# CORE.net
KiCad netlist of a schematic drawn in Altium Designer
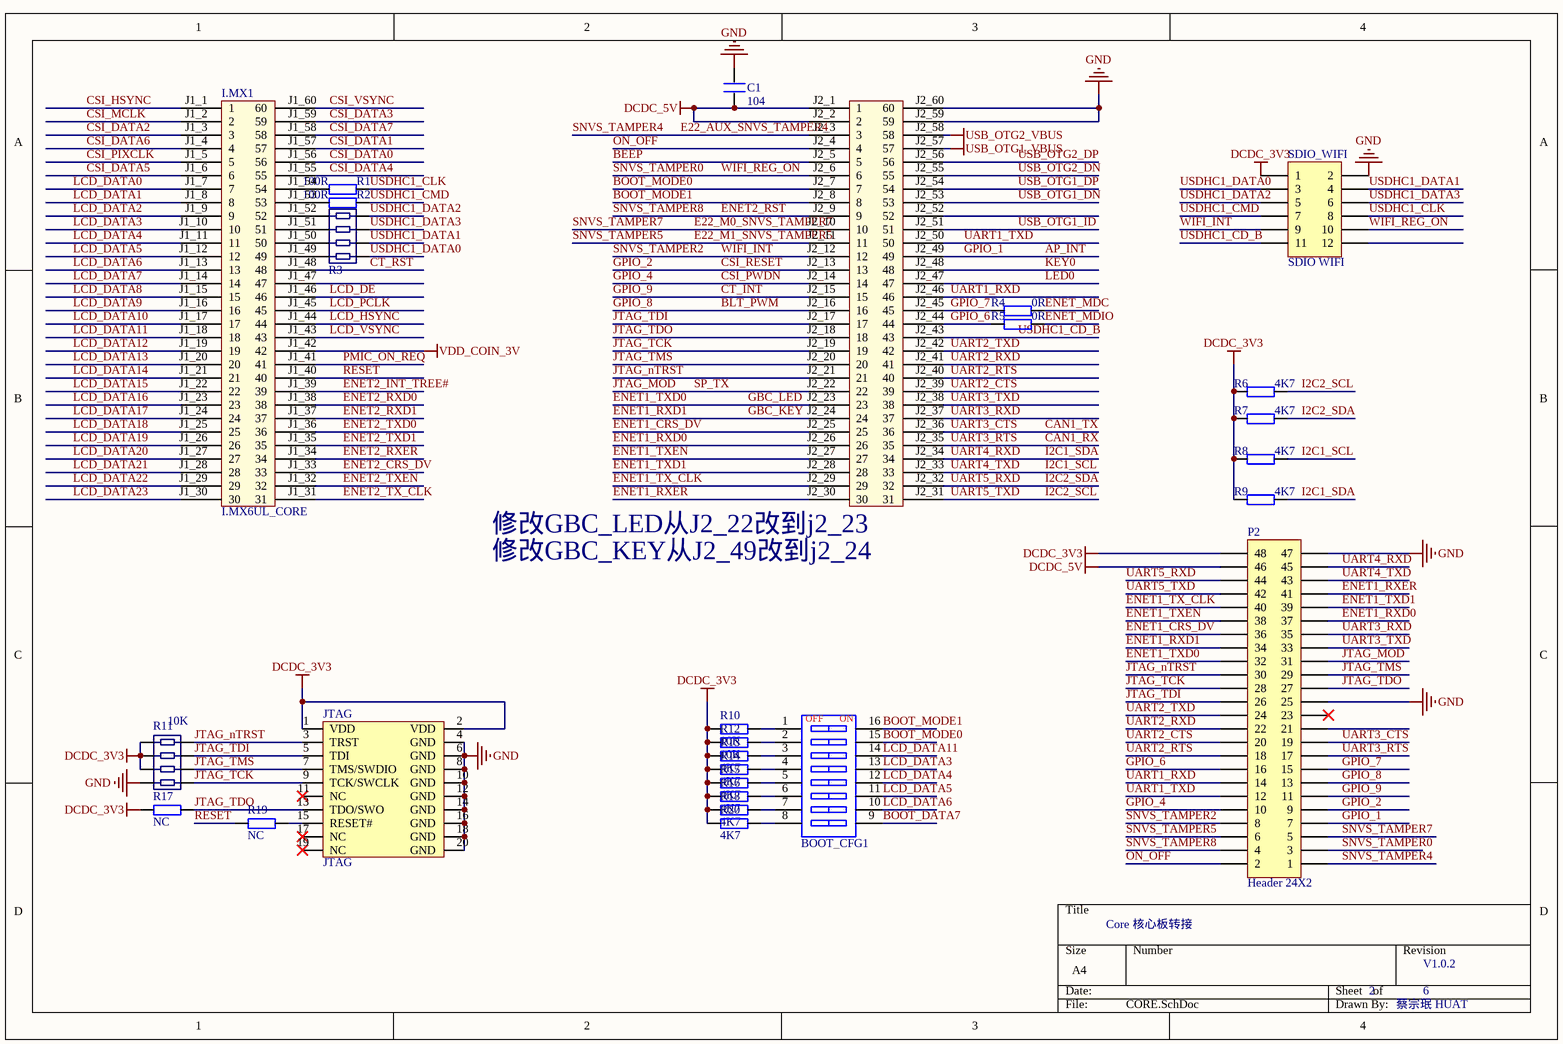
[diagram p0: CORE.SchDoc]

(export (version "E")
  (design (tool "Eeschema 10.0.6"))
  (components
    (comp (ref "BOOT_CFG1")
      (value "CSW-8P")
      (footprint "CSW DIP-8P")
      (description "8路编码开关")
      (fields (field (name "版权归属") "源创客"))
      (libsource (lib "IMX6UL_ALPHA(底板)_V2.0") (part "CSW-8P"))
    )
    (comp (ref "C1") (value "104") (footprint "C_0603P") (libsource (lib "ZZW封装汇总") (part "C")))
    (comp (ref "I.MX1")
      (value "I.MX6UL_CORE")
      (footprint "I.MX6UL_CORE")
      (description "I.MX6UL核心板")
      (libsource (lib "IMX6UL_ALPHA(底板)_V2.0") (part "I.MX6UL核心板"))
    )
    (comp (ref "JTAG") (value "JTAG") (footprint "JTAG_20") (libsource (lib "ZZW封装汇总") (part "JTAG")))
    (comp (ref "P2")
      (value "Header 24X2")
      (footprint "HDR2X24")
      (description "Header, 24-Pin, Dual row")
      (fields (field (name "PUBLISHER") "Altium Limited"))
      (libsource (lib "Miscellaneous Connectors") (part "Header 24X2"))
    )
    (comp (ref "R1") (value "100R") (footprint "R_0603P") (libsource (lib "ZZW封装汇总") (part "R")))
    (comp (ref "R2") (value "100R") (footprint "R_0603P") (libsource (lib "ZZW封装汇总") (part "R")))
    (comp (ref "R3")
      (value "R*4_0603_2")
      (footprint "R*4-0603")
      (libsource (lib "ZZW封装汇总") (part "R*4_0603_2"))
    )
    (comp (ref "R4") (value "0R") (footprint "R_0603P") (libsource (lib "ZZW封装汇总") (part "R")))
    (comp (ref "R5") (value "0R") (footprint "R_0603P") (libsource (lib "ZZW封装汇总") (part "R")))
    (comp (ref "R6") (value "4K7") (footprint "R_0603P") (libsource (lib "ZZW封装汇总") (part "R")))
    (comp (ref "R7") (value "4K7") (footprint "R_0603P") (libsource (lib "ZZW封装汇总") (part "R")))
    (comp (ref "R8") (value "4K7") (footprint "R_0603P") (libsource (lib "ZZW封装汇总") (part "R")))
    (comp (ref "R9") (value "4K7") (footprint "R_0603P") (libsource (lib "ZZW封装汇总") (part "R")))
    (comp (ref "R10") (value "10K") (footprint "R_0603P") (libsource (lib "ZZW封装汇总") (part "R")))
    (comp (ref "R11") (value "10K") (footprint "R*4-0603") (libsource (lib "ZZW封装汇总") (part "R*4_0603_2")))
    (comp (ref "R12") (value "10K") (footprint "R_0603P") (libsource (lib "ZZW封装汇总") (part "R")))
    (comp (ref "R13") (value "4K7") (footprint "R_0603P") (libsource (lib "ZZW封装汇总") (part "R")))
    (comp (ref "R14") (value "4K7") (footprint "R_0603P") (libsource (lib "ZZW封装汇总") (part "R")))
    (comp (ref "R15") (value "4K7") (footprint "R_0603P") (libsource (lib "ZZW封装汇总") (part "R")))
    (comp (ref "R16") (value "4K7") (footprint "R_0603P") (libsource (lib "ZZW封装汇总") (part "R")))
    (comp (ref "R17") (value "NC") (footprint "R_0603P") (libsource (lib "ZZW封装汇总") (part "R")))
    (comp (ref "R18") (value "4K7") (footprint "R_0603P") (libsource (lib "ZZW封装汇总") (part "R")))
    (comp (ref "R19") (value "NC") (footprint "R_0603P") (libsource (lib "ZZW封装汇总") (part "R")))
    (comp (ref "R20") (value "4K7") (footprint "R_0603P") (libsource (lib "ZZW封装汇总") (part "R")))
    (comp (ref "SDIO_WIFI")
      (value "SDIO WIFI")
      (footprint "HDR2X6")
      (description "Header, 6-Pin, Dual row")
      (fields (field (name "PUBLISHER") "Altium Limited"))
      (libsource (lib "IMX6UL_ALPHA(底板)_V2.0") (part "Header 6X2"))
    )
  )
  (nets
    (net (code "1") (name "/AP_INT") (class "Default")
      (node (ref "I.MX1") (pin "J2_49") (pinfunction "49_J2_49") (pintype "passive"))
      (node (ref "P2") (pin "7") (pinfunction "7_7") (pintype "passive"))
    )
    (net (code "2") (name "/BEEP") (class "Default")
      (node (ref "I.MX1") (pin "J2_5") (pinfunction "5_J2_5") (pintype "passive"))
    )
    (net (code "3") (name "/BLT_PWM") (class "Default")
      (node (ref "I.MX1") (pin "J2_16") (pinfunction "16_J2_16") (pintype "passive"))
      (node (ref "P2") (pin "13") (pinfunction "13_13") (pintype "passive"))
    )
    (net (code "4") (name "/BOOT_DATA7") (class "Default")
      (node (ref "BOOT_CFG1") (pin "9") (pinfunction "9_9") (pintype "passive"))
    )
    (net (code "5") (name "/BOOT_MODE0") (class "Default")
      (node (ref "BOOT_CFG1") (pin "15") (pinfunction "15_15") (pintype "passive"))
      (node (ref "I.MX1") (pin "J2_7") (pinfunction "7_J2_7") (pintype "passive"))
    )
    (net (code "6") (name "/BOOT_MODE1") (class "Default")
      (node (ref "BOOT_CFG1") (pin "16") (pinfunction "16_16") (pintype "passive"))
      (node (ref "I.MX1") (pin "J2_8") (pinfunction "8_J2_8") (pintype "passive"))
    )
    (net (code "7") (name "/CAN1_RX") (class "Default")
      (node (ref "I.MX1") (pin "J2_35") (pinfunction "35_J2_35") (pintype "passive"))
      (node (ref "P2") (pin "17") (pinfunction "17_17") (pintype "passive"))
    )
    (net (code "8") (name "/CAN1_TX") (class "Default")
      (node (ref "I.MX1") (pin "J2_36") (pinfunction "36_J2_36") (pintype "passive"))
      (node (ref "P2") (pin "19") (pinfunction "19_19") (pintype "passive"))
    )
    (net (code "9") (name "/CSI_DATA0") (class "Default")
      (node (ref "I.MX1") (pin "J1_56") (pinfunction "56_J1_56") (pintype "passive"))
    )
    (net (code "10") (name "/CSI_DATA1") (class "Default")
      (node (ref "I.MX1") (pin "J1_57") (pinfunction "57_J1_57") (pintype "passive"))
    )
    (net (code "11") (name "/CSI_DATA2") (class "Default")
      (node (ref "I.MX1") (pin "J1_3") (pinfunction "3_J1_3") (pintype "passive"))
    )
    (net (code "12") (name "/CSI_DATA3") (class "Default")
      (node (ref "I.MX1") (pin "J1_59") (pinfunction "59_J1_59") (pintype "passive"))
    )
    (net (code "13") (name "/CSI_DATA4") (class "Default")
      (node (ref "I.MX1") (pin "J1_55") (pinfunction "55_J1_55") (pintype "passive"))
    )
    (net (code "14") (name "/CSI_DATA5") (class "Default")
      (node (ref "I.MX1") (pin "J1_6") (pinfunction "6_J1_6") (pintype "passive"))
    )
    (net (code "15") (name "/CSI_DATA6") (class "Default")
      (node (ref "I.MX1") (pin "J1_4") (pinfunction "4_J1_4") (pintype "passive"))
    )
    (net (code "16") (name "/CSI_DATA7") (class "Default")
      (node (ref "I.MX1") (pin "J1_58") (pinfunction "58_J1_58") (pintype "passive"))
    )
    (net (code "17") (name "/CSI_HSYNC") (class "Default")
      (node (ref "I.MX1") (pin "J1_1") (pinfunction "1_J1_1") (pintype "passive"))
    )
    (net (code "18") (name "/CSI_MCLK") (class "Default")
      (node (ref "I.MX1") (pin "J1_2") (pinfunction "2_J1_2") (pintype "passive"))
    )
    (net (code "19") (name "/CSI_PIXCLK") (class "Default")
      (node (ref "I.MX1") (pin "J1_5") (pinfunction "5_J1_5") (pintype "passive"))
    )
    (net (code "20") (name "/CSI_PWDN") (class "Default")
      (node (ref "I.MX1") (pin "J2_14") (pinfunction "14_J2_14") (pintype "passive"))
      (node (ref "P2") (pin "10") (pinfunction "10_10") (pintype "passive"))
    )
    (net (code "21") (name "/CSI_RESET") (class "Default")
      (node (ref "I.MX1") (pin "J2_13") (pinfunction "13_J2_13") (pintype "passive"))
      (node (ref "P2") (pin "9") (pinfunction "9_9") (pintype "passive"))
    )
    (net (code "22") (name "/CSI_VSYNC") (class "Default")
      (node (ref "I.MX1") (pin "J1_60") (pinfunction "60_J1_60") (pintype "passive"))
    )
    (net (code "23") (name "/CT_INT") (class "Default")
      (node (ref "I.MX1") (pin "J2_15") (pinfunction "15_J2_15") (pintype "passive"))
      (node (ref "P2") (pin "11") (pinfunction "11_11") (pintype "passive"))
    )
    (net (code "24") (name "/CT_RST") (class "Default")
      (node (ref "I.MX1") (pin "J1_48") (pinfunction "48_J1_48") (pintype "passive"))
    )
    (net (code "25") (name "/E22_AUX_SNVS_TAMPER4") (class "Default")
      (node (ref "I.MX1") (pin "J2_3") (pinfunction "3_J2_3") (pintype "passive"))
      (node (ref "P2") (pin "1") (pinfunction "1_1") (pintype "passive"))
    )
    (net (code "26") (name "/E22_M0_SNVS_TAMPER7") (class "Default")
      (node (ref "I.MX1") (pin "J2_10") (pinfunction "10_J2_10") (pintype "passive"))
      (node (ref "P2") (pin "5") (pinfunction "5_5") (pintype "passive"))
    )
    (net (code "27") (name "/E22_M1_SNVS_TAMPER5") (class "Default")
      (node (ref "I.MX1") (pin "J2_11") (pinfunction "11_J2_11") (pintype "passive"))
      (node (ref "P2") (pin "6") (pinfunction "6_6") (pintype "passive"))
    )
    (net (code "28") (name "/ENET1_CRS_DV") (class "Default")
      (node (ref "I.MX1") (pin "J2_25") (pinfunction "25_J2_25") (pintype "passive"))
      (node (ref "P2") (pin "36") (pinfunction "36_36") (pintype "passive"))
    )
    (net (code "29") (name "/ENET1_RXD0") (class "Default")
      (node (ref "I.MX1") (pin "J2_26") (pinfunction "26_J2_26") (pintype "passive"))
      (node (ref "P2") (pin "37") (pinfunction "37_37") (pintype "passive"))
    )
    (net (code "30") (name "/ENET1_RXD1") (class "Default")
      (node (ref "I.MX1") (pin "J2_24") (pinfunction "24_J2_24") (pintype "passive"))
      (node (ref "P2") (pin "34") (pinfunction "34_34") (pintype "passive"))
    )
    (net (code "31") (name "/ENET1_RXER") (class "Default")
      (node (ref "I.MX1") (pin "J2_30") (pinfunction "30_J2_30") (pintype "passive"))
      (node (ref "P2") (pin "41") (pinfunction "41_41") (pintype "passive"))
    )
    (net (code "32") (name "/ENET1_TXD0") (class "Default")
      (node (ref "I.MX1") (pin "J2_23") (pinfunction "23_J2_23") (pintype "passive"))
      (node (ref "P2") (pin "32") (pinfunction "32_32") (pintype "passive"))
    )
    (net (code "33") (name "/ENET1_TXD1") (class "Default")
      (node (ref "I.MX1") (pin "J2_28") (pinfunction "28_J2_28") (pintype "passive"))
      (node (ref "P2") (pin "39") (pinfunction "39_39") (pintype "passive"))
    )
    (net (code "34") (name "/ENET1_TXEN") (class "Default")
      (node (ref "I.MX1") (pin "J2_27") (pinfunction "27_J2_27") (pintype "passive"))
      (node (ref "P2") (pin "38") (pinfunction "38_38") (pintype "passive"))
    )
    (net (code "35") (name "/ENET1_TX_CLK") (class "Default")
      (node (ref "I.MX1") (pin "J2_29") (pinfunction "29_J2_29") (pintype "passive"))
      (node (ref "P2") (pin "40") (pinfunction "40_40") (pintype "passive"))
    )
    (net (code "36") (name "/ENET2_CRS_DV") (class "Default")
      (node (ref "I.MX1") (pin "J1_33") (pinfunction "33_J1_33") (pintype "passive"))
    )
    (net (code "37") (name "/ENET2_INT_TREE#") (class "Default")
      (node (ref "I.MX1") (pin "J1_39") (pinfunction "39_J1_39") (pintype "passive"))
    )
    (net (code "38") (name "/ENET2_RST") (class "Default")
      (node (ref "I.MX1") (pin "J2_9") (pinfunction "9_J2_9") (pintype "passive"))
      (node (ref "P2") (pin "4") (pinfunction "4_4") (pintype "passive"))
    )
    (net (code "39") (name "/ENET2_RXD0") (class "Default")
      (node (ref "I.MX1") (pin "J1_38") (pinfunction "38_J1_38") (pintype "passive"))
    )
    (net (code "40") (name "/ENET2_RXD1") (class "Default")
      (node (ref "I.MX1") (pin "J1_37") (pinfunction "37_J1_37") (pintype "passive"))
    )
    (net (code "41") (name "/ENET2_RXER") (class "Default")
      (node (ref "I.MX1") (pin "J1_34") (pinfunction "34_J1_34") (pintype "passive"))
    )
    (net (code "42") (name "/ENET2_TXD0") (class "Default")
      (node (ref "I.MX1") (pin "J1_36") (pinfunction "36_J1_36") (pintype "passive"))
    )
    (net (code "43") (name "/ENET2_TXD1") (class "Default")
      (node (ref "I.MX1") (pin "J1_35") (pinfunction "35_J1_35") (pintype "passive"))
    )
    (net (code "44") (name "/ENET2_TXEN") (class "Default")
      (node (ref "I.MX1") (pin "J1_32") (pinfunction "32_J1_32") (pintype "passive"))
    )
    (net (code "45") (name "/ENET2_TX_CLK") (class "Default")
      (node (ref "I.MX1") (pin "J1_31") (pinfunction "31_J1_31") (pintype "passive"))
    )
    (net (code "46") (name "/ENET_MDC") (class "Default") (node (ref "R4") (pin "2") (pintype "passive")))
    (net (code "47") (name "/ENET_MDIO") (class "Default") (node (ref "R5") (pin "2") (pintype "passive")))
    (net (code "48") (name "/GPIO_6") (class "Default")
      (node (ref "I.MX1") (pin "J2_44") (pinfunction "44_J2_44") (pintype "passive"))
      (node (ref "P2") (pin "16") (pinfunction "16_16") (pintype "passive"))
      (node (ref "R5") (pin "1") (pintype "passive"))
    )
    (net (code "49") (name "/GPIO_7") (class "Default")
      (node (ref "I.MX1") (pin "J2_45") (pinfunction "45_J2_45") (pintype "passive"))
      (node (ref "P2") (pin "15") (pinfunction "15_15") (pintype "passive"))
      (node (ref "R4") (pin "1") (pintype "passive"))
    )
    (net (code "50") (name "/I2C1_SCL") (class "Default")
      (node (ref "I.MX1") (pin "J2_33") (pinfunction "33_J2_33") (pintype "passive"))
      (node (ref "P2") (pin "43") (pinfunction "43_43") (pintype "passive"))
      (node (ref "R8") (pin "2") (pintype "passive"))
    )
    (net (code "51") (name "/I2C1_SDA") (class "Default")
      (node (ref "I.MX1") (pin "J2_34") (pinfunction "34_J2_34") (pintype "passive"))
      (node (ref "P2") (pin "45") (pinfunction "45_45") (pintype "passive"))
      (node (ref "R9") (pin "2") (pintype "passive"))
    )
    (net (code "52") (name "/I2C2_SCL") (class "Default")
      (node (ref "I.MX1") (pin "J2_31") (pinfunction "31_J2_31") (pintype "passive"))
      (node (ref "P2") (pin "42") (pinfunction "42_42") (pintype "passive"))
      (node (ref "R6") (pin "2") (pintype "passive"))
    )
    (net (code "53") (name "/I2C2_SDA") (class "Default")
      (node (ref "I.MX1") (pin "J2_32") (pinfunction "32_J2_32") (pintype "passive"))
      (node (ref "P2") (pin "44") (pinfunction "44_44") (pintype "passive"))
      (node (ref "R7") (pin "2") (pintype "passive"))
    )
    (net (code "54") (name "/JTAG_MOD") (class "Default")
      (node (ref "I.MX1") (pin "J2_22") (pinfunction "22_J2_22") (pintype "passive"))
      (node (ref "P2") (pin "31") (pinfunction "31_31") (pintype "passive"))
    )
    (net (code "55") (name "/JTAG_TCK") (class "Default")
      (node (ref "I.MX1") (pin "J2_19") (pinfunction "19_J2_19") (pintype "passive"))
      (node (ref "JTAG") (pin "9") (pinfunction "TCK/SWCLK_9") (pintype "passive"))
      (node (ref "P2") (pin "28") (pinfunction "28_28") (pintype "passive"))
      (node (ref "R11") (pin "8") (pintype "passive"))
    )
    (net (code "56") (name "/JTAG_TDI") (class "Default")
      (node (ref "I.MX1") (pin "J2_17") (pinfunction "17_J2_17") (pintype "passive"))
      (node (ref "JTAG") (pin "5") (pinfunction "TDI_5") (pintype "passive"))
      (node (ref "P2") (pin "26") (pinfunction "26_26") (pintype "passive"))
      (node (ref "R11") (pin "4") (pintype "passive"))
    )
    (net (code "57") (name "/JTAG_TDO") (class "Default")
      (node (ref "I.MX1") (pin "J2_18") (pinfunction "18_J2_18") (pintype "passive"))
      (node (ref "JTAG") (pin "13") (pinfunction "TDO/SWO_13") (pintype "passive"))
      (node (ref "P2") (pin "27") (pinfunction "27_27") (pintype "passive"))
      (node (ref "R17") (pin "2") (pintype "passive"))
    )
    (net (code "58") (name "/JTAG_TMS") (class "Default")
      (node (ref "I.MX1") (pin "J2_20") (pinfunction "20_J2_20") (pintype "passive"))
      (node (ref "JTAG") (pin "7") (pinfunction "TMS/SWDIO_7") (pintype "passive"))
      (node (ref "P2") (pin "29") (pinfunction "29_29") (pintype "passive"))
      (node (ref "R11") (pin "6") (pintype "passive"))
    )
    (net (code "59") (name "/JTAG_nTRST") (class "Default")
      (node (ref "I.MX1") (pin "J2_21") (pinfunction "21_J2_21") (pintype "passive"))
      (node (ref "JTAG") (pin "3") (pinfunction "TRST_3") (pintype "passive"))
      (node (ref "P2") (pin "30") (pinfunction "30_30") (pintype "passive"))
      (node (ref "R11") (pin "2") (pintype "passive"))
    )
    (net (code "60") (name "/KEY0") (class "Default")
      (node (ref "I.MX1") (pin "J2_48") (pinfunction "48_J2_48") (pintype "passive"))
    )
    (net (code "61") (name "/LCD_DATA0") (class "Default")
      (node (ref "I.MX1") (pin "J1_7") (pinfunction "7_J1_7") (pintype "passive"))
    )
    (net (code "62") (name "/LCD_DATA1") (class "Default")
      (node (ref "I.MX1") (pin "J1_8") (pinfunction "8_J1_8") (pintype "passive"))
    )
    (net (code "63") (name "/LCD_DATA2") (class "Default")
      (node (ref "I.MX1") (pin "J1_9") (pinfunction "9_J1_9") (pintype "passive"))
    )
    (net (code "64") (name "/LCD_DATA3") (class "Default")
      (node (ref "BOOT_CFG1") (pin "13") (pinfunction "13_13") (pintype "passive"))
      (node (ref "I.MX1") (pin "J1_10") (pinfunction "10_J1_10") (pintype "passive"))
    )
    (net (code "65") (name "/LCD_DATA4") (class "Default")
      (node (ref "BOOT_CFG1") (pin "12") (pinfunction "12_12") (pintype "passive"))
      (node (ref "I.MX1") (pin "J1_11") (pinfunction "11_J1_11") (pintype "passive"))
    )
    (net (code "66") (name "/LCD_DATA5") (class "Default")
      (node (ref "BOOT_CFG1") (pin "11") (pinfunction "11_11") (pintype "passive"))
      (node (ref "I.MX1") (pin "J1_12") (pinfunction "12_J1_12") (pintype "passive"))
    )
    (net (code "67") (name "/LCD_DATA6") (class "Default")
      (node (ref "BOOT_CFG1") (pin "10") (pinfunction "10_10") (pintype "passive"))
      (node (ref "I.MX1") (pin "J1_13") (pinfunction "13_J1_13") (pintype "passive"))
    )
    (net (code "68") (name "/LCD_DATA7") (class "Default")
      (node (ref "I.MX1") (pin "J1_14") (pinfunction "14_J1_14") (pintype "passive"))
    )
    (net (code "69") (name "/LCD_DATA8") (class "Default")
      (node (ref "I.MX1") (pin "J1_15") (pinfunction "15_J1_15") (pintype "passive"))
    )
    (net (code "70") (name "/LCD_DATA9") (class "Default")
      (node (ref "I.MX1") (pin "J1_16") (pinfunction "16_J1_16") (pintype "passive"))
    )
    (net (code "71") (name "/LCD_DATA10") (class "Default")
      (node (ref "I.MX1") (pin "J1_17") (pinfunction "17_J1_17") (pintype "passive"))
    )
    (net (code "72") (name "/LCD_DATA11") (class "Default")
      (node (ref "BOOT_CFG1") (pin "14") (pinfunction "14_14") (pintype "passive"))
      (node (ref "I.MX1") (pin "J1_18") (pinfunction "18_J1_18") (pintype "passive"))
    )
    (net (code "73") (name "/LCD_DATA12") (class "Default")
      (node (ref "I.MX1") (pin "J1_19") (pinfunction "19_J1_19") (pintype "passive"))
    )
    (net (code "74") (name "/LCD_DATA13") (class "Default")
      (node (ref "I.MX1") (pin "J1_20") (pinfunction "20_J1_20") (pintype "passive"))
    )
    (net (code "75") (name "/LCD_DATA14") (class "Default")
      (node (ref "I.MX1") (pin "J1_21") (pinfunction "21_J1_21") (pintype "passive"))
    )
    (net (code "76") (name "/LCD_DATA15") (class "Default")
      (node (ref "I.MX1") (pin "J1_22") (pinfunction "22_J1_22") (pintype "passive"))
    )
    (net (code "77") (name "/LCD_DATA16") (class "Default")
      (node (ref "I.MX1") (pin "J1_23") (pinfunction "23_J1_23") (pintype "passive"))
    )
    (net (code "78") (name "/LCD_DATA17") (class "Default")
      (node (ref "I.MX1") (pin "J1_24") (pinfunction "24_J1_24") (pintype "passive"))
    )
    (net (code "79") (name "/LCD_DATA18") (class "Default")
      (node (ref "I.MX1") (pin "J1_25") (pinfunction "25_J1_25") (pintype "passive"))
    )
    (net (code "80") (name "/LCD_DATA19") (class "Default")
      (node (ref "I.MX1") (pin "J1_26") (pinfunction "26_J1_26") (pintype "passive"))
    )
    (net (code "81") (name "/LCD_DATA20") (class "Default")
      (node (ref "I.MX1") (pin "J1_27") (pinfunction "27_J1_27") (pintype "passive"))
    )
    (net (code "82") (name "/LCD_DATA21") (class "Default")
      (node (ref "I.MX1") (pin "J1_28") (pinfunction "28_J1_28") (pintype "passive"))
    )
    (net (code "83") (name "/LCD_DATA22") (class "Default")
      (node (ref "I.MX1") (pin "J1_29") (pinfunction "29_J1_29") (pintype "passive"))
    )
    (net (code "84") (name "/LCD_DATA23") (class "Default")
      (node (ref "I.MX1") (pin "J1_30") (pinfunction "30_J1_30") (pintype "passive"))
    )
    (net (code "85") (name "/LCD_DE") (class "Default")
      (node (ref "I.MX1") (pin "J1_46") (pinfunction "46_J1_46") (pintype "passive"))
    )
    (net (code "86") (name "/LCD_HSYNC") (class "Default")
      (node (ref "I.MX1") (pin "J1_44") (pinfunction "44_J1_44") (pintype "passive"))
    )
    (net (code "87") (name "/LCD_PCLK") (class "Default")
      (node (ref "I.MX1") (pin "J1_45") (pinfunction "45_J1_45") (pintype "passive"))
    )
    (net (code "88") (name "/LCD_VSYNC") (class "Default")
      (node (ref "I.MX1") (pin "J1_43") (pinfunction "43_J1_43") (pintype "passive"))
    )
    (net (code "89") (name "/LED0") (class "Default")
      (node (ref "I.MX1") (pin "J2_47") (pinfunction "47_J2_47") (pintype "passive"))
    )
    (net (code "90") (name "/ON_OFF") (class "Default")
      (node (ref "I.MX1") (pin "J2_4") (pinfunction "4_J2_4") (pintype "passive"))
      (node (ref "P2") (pin "2") (pinfunction "2_2") (pintype "passive"))
    )
    (net (code "91") (name "/PMIC_ON_REQ") (class "Default")
      (node (ref "I.MX1") (pin "J1_41") (pinfunction "41_J1_41") (pintype "passive"))
    )
    (net (code "92") (name "/RESET") (class "Default")
      (node (ref "I.MX1") (pin "J1_40") (pinfunction "40_J1_40") (pintype "passive"))
      (node (ref "R19") (pin "1") (pintype "passive"))
    )
    (net (code "93") (name "/SNVS_TAMPER0") (class "Default")
      (node (ref "I.MX1") (pin "J2_6") (pinfunction "6_J2_6") (pintype "passive"))
      (node (ref "P2") (pin "3") (pinfunction "3_3") (pintype "passive"))
      (node (ref "SDIO_WIFI") (pin "10") (pinfunction "10_10") (pintype "passive"))
    )
    (net (code "94") (name "/SNVS_TAMPER2") (class "Default")
      (node (ref "I.MX1") (pin "J2_12") (pinfunction "12_J2_12") (pintype "passive"))
      (node (ref "P2") (pin "8") (pinfunction "8_8") (pintype "passive"))
      (node (ref "SDIO_WIFI") (pin "9") (pinfunction "9_9") (pintype "passive"))
    )
    (net (code "95") (name "/UART1_RXD") (class "Default")
      (node (ref "I.MX1") (pin "J2_46") (pinfunction "46_J2_46") (pintype "passive"))
      (node (ref "P2") (pin "14") (pinfunction "14_14") (pintype "passive"))
    )
    (net (code "96") (name "/UART1_TXD") (class "Default")
      (node (ref "I.MX1") (pin "J2_50") (pinfunction "50_J2_50") (pintype "passive"))
      (node (ref "P2") (pin "12") (pinfunction "12_12") (pintype "passive"))
    )
    (net (code "97") (name "/UART2_CTS") (class "Default")
      (node (ref "I.MX1") (pin "J2_39") (pinfunction "39_J2_39") (pintype "passive"))
      (node (ref "P2") (pin "20") (pinfunction "20_20") (pintype "passive"))
    )
    (net (code "98") (name "/UART2_RTS") (class "Default")
      (node (ref "I.MX1") (pin "J2_40") (pinfunction "40_J2_40") (pintype "passive"))
      (node (ref "P2") (pin "18") (pinfunction "18_18") (pintype "passive"))
    )
    (net (code "99") (name "/UART2_RXD") (class "Default")
      (node (ref "I.MX1") (pin "J2_41") (pinfunction "41_J2_41") (pintype "passive"))
      (node (ref "P2") (pin "22") (pinfunction "22_22") (pintype "passive"))
    )
    (net (code "100") (name "/UART2_TXD") (class "Default")
      (node (ref "I.MX1") (pin "J2_42") (pinfunction "42_J2_42") (pintype "passive"))
      (node (ref "P2") (pin "24") (pinfunction "24_24") (pintype "passive"))
    )
    (net (code "101") (name "/UART3_RXD") (class "Default")
      (node (ref "I.MX1") (pin "J2_37") (pinfunction "37_J2_37") (pintype "passive"))
      (node (ref "P2") (pin "35") (pinfunction "35_35") (pintype "passive"))
    )
    (net (code "102") (name "/UART3_TXD") (class "Default")
      (node (ref "I.MX1") (pin "J2_38") (pinfunction "38_J2_38") (pintype "passive"))
      (node (ref "P2") (pin "33") (pinfunction "33_33") (pintype "passive"))
    )
    (net (code "103") (name "/USB_OTG1_DN") (class "Default")
      (node (ref "I.MX1") (pin "J2_53") (pinfunction "53_J2_53") (pintype "passive"))
    )
    (net (code "104") (name "/USB_OTG1_DP") (class "Default")
      (node (ref "I.MX1") (pin "J2_54") (pinfunction "54_J2_54") (pintype "passive"))
    )
    (net (code "105") (name "/USB_OTG1_ID") (class "Default")
      (node (ref "I.MX1") (pin "J2_51") (pinfunction "51_J2_51") (pintype "passive"))
    )
    (net (code "106") (name "/USB_OTG2_DN") (class "Default")
      (node (ref "I.MX1") (pin "J2_55") (pinfunction "55_J2_55") (pintype "passive"))
    )
    (net (code "107") (name "/USB_OTG2_DP") (class "Default")
      (node (ref "I.MX1") (pin "J2_56") (pinfunction "56_J2_56") (pintype "passive"))
    )
    (net (code "108") (name "/USDHC1_CD_B") (class "Default")
      (node (ref "I.MX1") (pin "J2_43") (pinfunction "43_J2_43") (pintype "passive"))
      (node (ref "SDIO_WIFI") (pin "11") (pinfunction "11_11") (pintype "passive"))
    )
    (net (code "109") (name "/USDHC1_CLK") (class "Default")
      (node (ref "R1") (pin "2") (pintype "passive"))
      (node (ref "SDIO_WIFI") (pin "8") (pinfunction "8_8") (pintype "passive"))
    )
    (net (code "110") (name "/USDHC1_CMD") (class "Default")
      (node (ref "R2") (pin "2") (pintype "passive"))
      (node (ref "SDIO_WIFI") (pin "7") (pinfunction "7_7") (pintype "passive"))
    )
    (net (code "111") (name "/USDHC1_DATA0") (class "Default")
      (node (ref "R3") (pin "8") (pintype "passive"))
      (node (ref "SDIO_WIFI") (pin "3") (pinfunction "3_3") (pintype "passive"))
    )
    (net (code "112") (name "/USDHC1_DATA1") (class "Default")
      (node (ref "R3") (pin "6") (pintype "passive"))
      (node (ref "SDIO_WIFI") (pin "4") (pinfunction "4_4") (pintype "passive"))
    )
    (net (code "113") (name "/USDHC1_DATA2") (class "Default")
      (node (ref "R3") (pin "2") (pintype "passive"))
      (node (ref "SDIO_WIFI") (pin "5") (pinfunction "5_5") (pintype "passive"))
    )
    (net (code "114") (name "/USDHC1_DATA3") (class "Default")
      (node (ref "R3") (pin "4") (pintype "passive"))
      (node (ref "SDIO_WIFI") (pin "6") (pinfunction "6_6") (pintype "passive"))
    )
    (net (code "115") (name "DCDC_3V3") (class "Default")
      (node (ref "JTAG") (pin "1") (pinfunction "VDD_1") (pintype "passive"))
      (node (ref "JTAG") (pin "2") (pinfunction "VDD_2") (pintype "passive"))
      (node (ref "P2") (pin "48") (pinfunction "48_48") (pintype "passive"))
      (node (ref "R10") (pin "1") (pintype "passive"))
      (node (ref "R11") (pin "1") (pintype "passive"))
      (node (ref "R11") (pin "3") (pintype "passive"))
      (node (ref "R11") (pin "5") (pintype "passive"))
      (node (ref "R12") (pin "1") (pintype "passive"))
      (node (ref "R13") (pin "1") (pintype "passive"))
      (node (ref "R14") (pin "1") (pintype "passive"))
      (node (ref "R15") (pin "1") (pintype "passive"))
      (node (ref "R16") (pin "1") (pintype "passive"))
      (node (ref "R17") (pin "1") (pintype "passive"))
      (node (ref "R18") (pin "1") (pintype "passive"))
      (node (ref "R20") (pin "1") (pintype "passive"))
      (node (ref "R6") (pin "1") (pintype "passive"))
      (node (ref "R7") (pin "1") (pintype "passive"))
      (node (ref "R8") (pin "1") (pintype "passive"))
      (node (ref "R9") (pin "1") (pintype "passive"))
      (node (ref "SDIO_WIFI") (pin "1") (pinfunction "1_1") (pintype "passive"))
    )
    (net (code "116") (name "DCDC_5V") (class "Default")
      (node (ref "C1") (pin "1") (pintype "passive"))
      (node (ref "I.MX1") (pin "J2_1") (pinfunction "1_J2_1") (pintype "passive"))
      (node (ref "I.MX1") (pin "J2_2") (pinfunction "2_J2_2") (pintype "passive"))
      (node (ref "P2") (pin "46") (pinfunction "46_46") (pintype "passive"))
    )
    (net (code "117") (name "GND") (class "Default")
      (node (ref "C1") (pin "2") (pintype "passive"))
      (node (ref "I.MX1") (pin "J2_59") (pinfunction "59_J2_59") (pintype "passive"))
      (node (ref "I.MX1") (pin "J2_60") (pinfunction "60_J2_60") (pintype "passive"))
      (node (ref "JTAG") (pin "10") (pinfunction "GND_10") (pintype "passive"))
      (node (ref "JTAG") (pin "12") (pinfunction "GND_12") (pintype "passive"))
      (node (ref "JTAG") (pin "14") (pinfunction "GND_14") (pintype "passive"))
      (node (ref "JTAG") (pin "16") (pinfunction "GND_16") (pintype "passive"))
      (node (ref "JTAG") (pin "18") (pinfunction "GND_18") (pintype "passive"))
      (node (ref "JTAG") (pin "20") (pinfunction "GND_20") (pintype "passive"))
      (node (ref "JTAG") (pin "4") (pinfunction "GND_4") (pintype "passive"))
      (node (ref "JTAG") (pin "6") (pinfunction "GND_6") (pintype "passive"))
      (node (ref "JTAG") (pin "8") (pinfunction "GND_8") (pintype "passive"))
      (node (ref "P2") (pin "25") (pinfunction "25_25") (pintype "passive"))
      (node (ref "P2") (pin "47") (pinfunction "47_47") (pintype "passive"))
      (node (ref "R11") (pin "7") (pintype "passive"))
      (node (ref "SDIO_WIFI") (pin "2") (pinfunction "2_2") (pintype "passive"))
    )
    (net (code "118") (name "Net-(BOOT_CFG1-Pad1)") (class "Default")
      (node (ref "BOOT_CFG1") (pin "1") (pinfunction "1_1") (pintype "passive"))
      (node (ref "R10") (pin "2") (pintype "passive"))
    )
    (net (code "119") (name "Net-(BOOT_CFG1-Pad2)") (class "Default")
      (node (ref "BOOT_CFG1") (pin "2") (pinfunction "2_2") (pintype "passive"))
      (node (ref "R12") (pin "2") (pintype "passive"))
    )
    (net (code "120") (name "Net-(BOOT_CFG1-Pad3)") (class "Default")
      (node (ref "BOOT_CFG1") (pin "3") (pinfunction "3_3") (pintype "passive"))
      (node (ref "R13") (pin "2") (pintype "passive"))
    )
    (net (code "121") (name "Net-(BOOT_CFG1-Pad4)") (class "Default")
      (node (ref "BOOT_CFG1") (pin "4") (pinfunction "4_4") (pintype "passive"))
      (node (ref "R14") (pin "2") (pintype "passive"))
    )
    (net (code "122") (name "Net-(BOOT_CFG1-Pad5)") (class "Default")
      (node (ref "BOOT_CFG1") (pin "5") (pinfunction "5_5") (pintype "passive"))
      (node (ref "R15") (pin "2") (pintype "passive"))
    )
    (net (code "123") (name "Net-(BOOT_CFG1-Pad6)") (class "Default")
      (node (ref "BOOT_CFG1") (pin "6") (pinfunction "6_6") (pintype "passive"))
      (node (ref "R16") (pin "2") (pintype "passive"))
    )
    (net (code "124") (name "Net-(BOOT_CFG1-Pad7)") (class "Default")
      (node (ref "BOOT_CFG1") (pin "7") (pinfunction "7_7") (pintype "passive"))
      (node (ref "R18") (pin "2") (pintype "passive"))
    )
    (net (code "125") (name "Net-(BOOT_CFG1-Pad8)") (class "Default")
      (node (ref "BOOT_CFG1") (pin "8") (pinfunction "8_8") (pintype "passive"))
      (node (ref "R20") (pin "2") (pintype "passive"))
    )
    (net (code "126") (name "Net-(I.MX1-49-PadJ1_49)") (class "Default")
      (node (ref "I.MX1") (pin "J1_49") (pinfunction "49_J1_49") (pintype "passive"))
      (node (ref "R3") (pin "7") (pintype "passive"))
    )
    (net (code "127") (name "Net-(I.MX1-50-PadJ1_50)") (class "Default")
      (node (ref "I.MX1") (pin "J1_50") (pinfunction "50_J1_50") (pintype "passive"))
      (node (ref "R3") (pin "5") (pintype "passive"))
    )
    (net (code "128") (name "Net-(I.MX1-51-PadJ1_51)") (class "Default")
      (node (ref "I.MX1") (pin "J1_51") (pinfunction "51_J1_51") (pintype "passive"))
      (node (ref "R3") (pin "3") (pintype "passive"))
    )
    (net (code "129") (name "Net-(I.MX1-52-PadJ1_52)") (class "Default")
      (node (ref "I.MX1") (pin "J1_52") (pinfunction "52_J1_52") (pintype "passive"))
      (node (ref "R3") (pin "1") (pintype "passive"))
    )
    (net (code "130") (name "Net-(I.MX1-53-PadJ1_53)") (class "Default")
      (node (ref "I.MX1") (pin "J1_53") (pinfunction "53_J1_53") (pintype "passive"))
      (node (ref "R2") (pin "1") (pintype "passive"))
    )
    (net (code "131") (name "Net-(I.MX1-54-PadJ1_54)") (class "Default")
      (node (ref "I.MX1") (pin "J1_54") (pinfunction "54_J1_54") (pintype "passive"))
      (node (ref "R1") (pin "1") (pintype "passive"))
    )
    (net (code "132") (name "Net-(JTAG-RESET#)") (class "Default")
      (node (ref "JTAG") (pin "15") (pinfunction "RESET#_15") (pintype "passive"))
      (node (ref "R19") (pin "2") (pintype "passive"))
    )
    (net (code "133") (name "USB_OTG1_VBUS") (class "Default")
      (node (ref "I.MX1") (pin "J2_57") (pinfunction "57_J2_57") (pintype "passive"))
    )
    (net (code "134") (name "USB_OTG2_VBUS") (class "Default")
      (node (ref "I.MX1") (pin "J2_58") (pinfunction "58_J2_58") (pintype "passive"))
    )
    (net (code "135") (name "VDD_COIN_3V") (class "Default")
      (node (ref "I.MX1") (pin "J1_42") (pinfunction "42_J1_42") (pintype "passive"))
    )
    (net (code "136") (name "unconnected-(I.MX1-47-PadJ1_47)") (class "Default")
      (node (ref "I.MX1") (pin "J1_47") (pinfunction "47_J1_47") (pintype "passive"))
    )
    (net (code "137") (name "unconnected-(I.MX1-52-PadJ2_52)") (class "Default")
      (node (ref "I.MX1") (pin "J2_52") (pinfunction "52_J2_52") (pintype "passive"))
    )
    (net (code "138") (name "unconnected-(JTAG-NC-Pad11)") (class "Default")
      (node (ref "JTAG") (pin "11") (pinfunction "NC_11") (pintype "passive+no_connect"))
    )
    (net (code "139") (name "unconnected-(JTAG-NC-Pad17)") (class "Default")
      (node (ref "JTAG") (pin "17") (pinfunction "NC_17") (pintype "passive+no_connect"))
    )
    (net (code "140") (name "unconnected-(JTAG-NC-Pad19)") (class "Default")
      (node (ref "JTAG") (pin "19") (pinfunction "NC_19") (pintype "passive+no_connect"))
    )
    (net (code "141") (name "unconnected-(P2-Pad21)") (class "Default")
      (node (ref "P2") (pin "21") (pinfunction "21_21") (pintype "passive"))
    )
    (net (code "142") (name "unconnected-(P2-Pad23)") (class "Default")
      (node (ref "P2") (pin "23") (pinfunction "23_23") (pintype "passive+no_connect"))
    )
    (net (code "143") (name "unconnected-(SDIO_WIFI-Pad12)") (class "Default")
      (node (ref "SDIO_WIFI") (pin "12") (pinfunction "12_12") (pintype "passive"))
    )
  )
)
